# attiny_45_noise_ldr.net
KiCad netlist of a schematic drawn in EAGLE
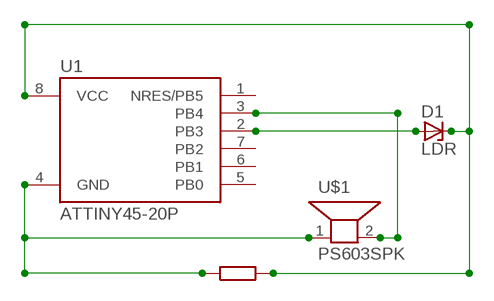
[diagram p0: schematic, sheet 1]

(export (version "E")
  (design (tool "Eeschema 10.0.6"))
  (components
    (comp (ref "D1")
      (value "LDR")
      (footprint "eagle-import:DO35Z10")
      (libsource (lib "eagle-import") (part "1N821"))
    )
    (comp (ref "U$1")
      (value "PS603SPK")
      (footprint "eagle-import:PS603")
      (libsource (lib "eagle-import") (part "PS603SPK"))
    )
    (comp (ref "U1")
      (value "ATTINY45-20P")
      (footprint "eagle-import:PDIP08_300MIL")
      (libsource (lib "eagle-import") (part "ATTINY45P-20"))
    )
  )
  (nets
    (net (code "1") (name "Net-(U1-GND)") (class "Default")
      (node (ref "U$1") (pin "1") (pinfunction "1_1") (pintype "passive"))
      (node (ref "U1") (pin "4") (pinfunction "GND_4") (pintype "power_in"))
    )
    (net (code "2") (name "Net-(U1-PB3)") (class "Default")
      (node (ref "D1") (pin "A") (pinfunction "A_A") (pintype "passive"))
      (node (ref "U1") (pin "2") (pinfunction "PB3_2") (pintype "bidirectional"))
    )
    (net (code "3") (name "Net-(U1-PB4)") (class "Default")
      (node (ref "U$1") (pin "2") (pinfunction "2_2") (pintype "passive"))
      (node (ref "U1") (pin "3") (pinfunction "PB4_3") (pintype "bidirectional"))
    )
    (net (code "4") (name "Net-(U1-VCC)") (class "Default")
      (node (ref "D1") (pin "C") (pinfunction "C_C") (pintype "passive"))
      (node (ref "U1") (pin "8") (pinfunction "VCC_8") (pintype "power_in"))
    )
    (net (code "5") (name "unconnected-(U1-NRES{slash}PB5-Pad1)") (class "Default")
      (node (ref "U1") (pin "1") (pinfunction "NRES/PB5_1") (pintype "bidirectional"))
    )
    (net (code "6") (name "unconnected-(U1-PB0-Pad5)") (class "Default")
      (node (ref "U1") (pin "5") (pinfunction "PB0_5") (pintype "bidirectional"))
    )
    (net (code "7") (name "unconnected-(U1-PB1-Pad6)") (class "Default")
      (node (ref "U1") (pin "6") (pinfunction "PB1_6") (pintype "bidirectional"))
    )
    (net (code "8") (name "unconnected-(U1-PB2-Pad7)") (class "Default")
      (node (ref "U1") (pin "7") (pinfunction "PB2_7") (pintype "bidirectional"))
    )
  )
)
